# ESP_Circuit.net
KiCad netlist of a schematic drawn in Altium Designer
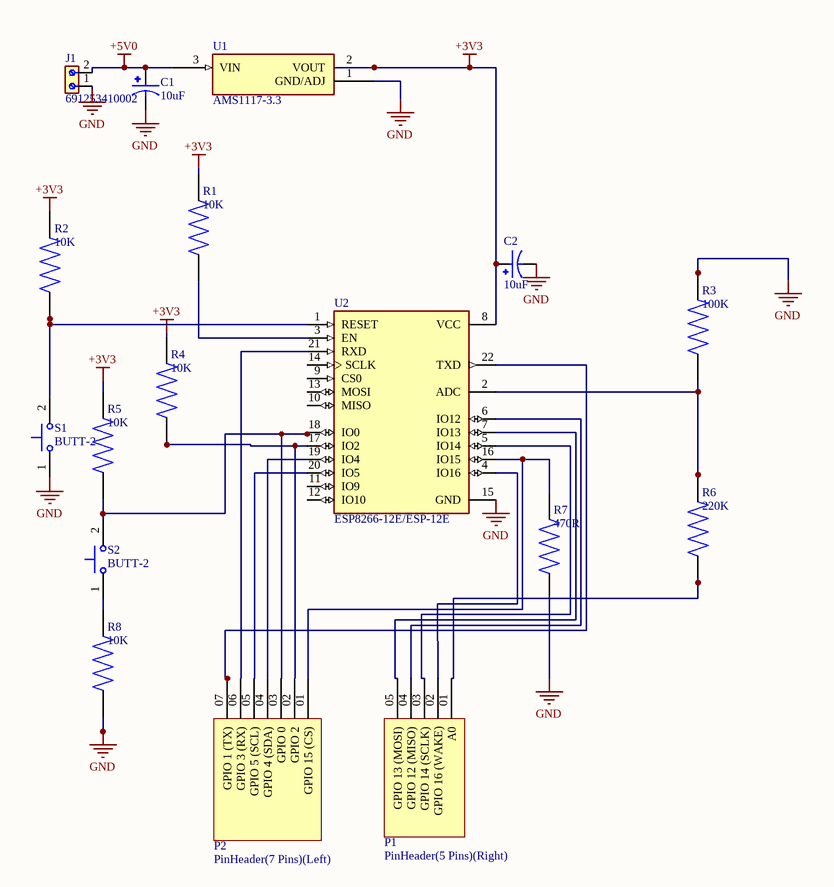
[diagram p0: ESP_Circuit.SchDoc]

(export (version "E")
  (design (tool "Eeschema 10.0.6"))
  (components
    (comp (ref "C1")
      (value "10uF")
      (footprint "CAPPRD500W60D1000H2000")
      (description "Aluminum Electrolytic Capacitors - Radial Leaded 10uF 350volts AEC-Q200")
      (fields (field (name "MF") "Panasonic") (field (name "MP") "EEU-EB2V100B"))
      (libsource (lib "MegaProject_Lib") (part "EEUEB2V100B"))
    )
    (comp (ref "C2")
      (value "10uF")
      (footprint "CAPPRD500W60D1000H2000")
      (description "Aluminum Electrolytic Capacitors - Radial Leaded 10uF 350volts AEC-Q200")
      (fields (field (name "MF") "Panasonic") (field (name "MP") "EEU-EB2V100B"))
      (libsource (lib "") (part "EEUEB2V100B_1"))
    )
    (comp (ref "J1")
      (value "691253410002")
      (footprint "691253410002")
      (description "7.62 MM TERMINAL BLOCK, HORIZONT")
      (fields (field (name "MF") "WÃ¼rth Elektronik"))
      (libsource (lib "MegaProject_Lib") (part "691253410002"))
    )
    (comp (ref "P1")
      (value "PinHeader(5 Pins)(Right)")
      (footprint "5 pins connector")
      (libsource (lib "MegaProject_Lib") (part "PinHeader(5 Pins)(Right)"))
    )
    (comp (ref "P2")
      (value "PinHeader(7 Pins)(Left)")
      (footprint "7 pins connector")
      (libsource (lib "MegaProject_Lib") (part "PinHeader(7 Pins)(Left)"))
    )
    (comp (ref "R1")
      (value "10K")
      (footprint "RESAD1100W55L680D260")
      (description "RES 280K OHM 1/4W 1% AXIAL")
      (fields (field (name "MP") "MFR-25FBF52-3K16"))
      (libsource (lib "MegaProject_Lib") (part "MFR-25FBF52-3K16"))
    )
    (comp (ref "R2")
      (value "10K")
      (footprint "RESAD1100W55L680D260")
      (description "RES 280K OHM 1/4W 1% AXIAL")
      (fields (field (name "MP") "MFR-25FBF52-3K16"))
      (libsource (lib "MegaProject_Lib") (part "MFR-25FBF52-3K16"))
    )
    (comp (ref "R3")
      (value "100K")
      (footprint "RESAD1100W55L680D260")
      (description "RES 280K OHM 1/4W 1% AXIAL")
      (fields (field (name "MP") "MFR-25FBF52-3K16"))
      (libsource (lib "MegaProject_Lib") (part "MFR-25FBF52-3K16"))
    )
    (comp (ref "R4")
      (value "10K")
      (footprint "RESAD1100W55L680D260")
      (description "RES 280K OHM 1/4W 1% AXIAL")
      (fields (field (name "MP") "MFR-25FBF52-3K16"))
      (libsource (lib "MegaProject_Lib") (part "MFR-25FBF52-3K16"))
    )
    (comp (ref "R5")
      (value "10K")
      (footprint "RESAD1100W55L680D260")
      (description "RES 280K OHM 1/4W 1% AXIAL")
      (fields (field (name "MP") "MFR-25FBF52-3K16"))
      (libsource (lib "MegaProject_Lib") (part "MFR-25FBF52-3K16"))
    )
    (comp (ref "R6")
      (value "220K")
      (footprint "RESAD1100W55L680D260")
      (description "RES 280K OHM 1/4W 1% AXIAL")
      (fields (field (name "MP") "MFR-25FBF52-3K16"))
      (libsource (lib "MegaProject_Lib") (part "MFR-25FBF52-3K16"))
    )
    (comp (ref "R7")
      (value "470R")
      (footprint "RESAD1100W55L680D260")
      (description "RES 280K OHM 1/4W 1% AXIAL")
      (fields (field (name "MP") "MFR-25FBF52-3K16"))
      (libsource (lib "MegaProject_Lib") (part "MFR-25FBF52-3K16"))
    )
    (comp (ref "R8")
      (value "10K")
      (footprint "RESAD1100W55L680D260")
      (description "RES 280K OHM 1/4W 1% AXIAL")
      (fields (field (name "MP") "MFR-25FBF52-3K16"))
      (libsource (lib "MegaProject_Lib") (part "MFR-25FBF52-3K16"))
    )
    (comp (ref "S1")
      (value "BUTT-2")
      (footprint "SW_BUTT-2")
      (description "Tactile Switches MINI PUSH BUTTON SWITCH 2-PIN QTY. 4")
      (fields (field (name "MF") "Gravitech"))
      (libsource (lib "MegaProject_Lib") (part "BUTT-2"))
    )
    (comp (ref "S2")
      (value "BUTT-2")
      (footprint "SW_BUTT-2")
      (description "Tactile Switches MINI PUSH BUTTON SWITCH 2-PIN QTY. 4")
      (fields (field (name "MF") "Gravitech"))
      (libsource (lib "MegaProject_Lib") (part "BUTT-2"))
    )
    (comp (ref "U1")
      (value "AMS1117-3.3")
      (footprint "SOT229P700X180-4N")
      (description "Sot223/Pkg 1-Amp 3.3-Volt Low Drop Out Voltage Regulatator")
      (fields (field (name "MF") "Advanced Monolithic Systems"))
      (libsource (lib "MegaProject_Lib") (part "AMS1117-3.3"))
    )
    (comp (ref "U2")
      (value "ESP8266-12E/ESP-12E")
      (footprint "XCVR_ESP8266-12E/ESP-12E")
      (fields (field (name "MF") "AI-Thinker"))
      (libsource (lib "MegaProject_Lib") (part "ESP8266-12E/ESP-12E"))
    )
  )
  (nets
    (net (code "1") (name "+3V3") (class "Default")
      (node (ref "C2") (pin "P") (pinfunction "P_P") (pintype "passive"))
      (node (ref "R1") (pin "2") (pinfunction "2_2") (pintype "passive"))
      (node (ref "R2") (pin "2") (pinfunction "2_2") (pintype "passive"))
      (node (ref "R4") (pin "2") (pinfunction "2_2") (pintype "passive"))
      (node (ref "R5") (pin "2") (pinfunction "2_2") (pintype "passive"))
      (node (ref "U1") (pin "2") (pinfunction "VOUT_2") (pintype "power_in"))
      (node (ref "U2") (pin "8") (pinfunction "VCC_8") (pintype "power_in"))
    )
    (net (code "2") (name "+5V0") (class "Default")
      (node (ref "C1") (pin "P") (pinfunction "P_P") (pintype "passive"))
      (node (ref "J1") (pin "2") (pinfunction "2_2") (pintype "passive"))
      (node (ref "U1") (pin "3") (pinfunction "VIN_3") (pintype "input"))
    )
    (net (code "3") (name "GND") (class "Default")
      (node (ref "C1") (pin "N") (pinfunction "N_N") (pintype "passive"))
      (node (ref "C2") (pin "N") (pinfunction "N_N") (pintype "passive"))
      (node (ref "J1") (pin "1") (pinfunction "1_1") (pintype "passive"))
      (node (ref "R3") (pin "2") (pinfunction "2_2") (pintype "passive"))
      (node (ref "R7") (pin "1") (pinfunction "1_1") (pintype "passive"))
      (node (ref "R8") (pin "1") (pinfunction "1_1") (pintype "passive"))
      (node (ref "S1") (pin "1") (pinfunction "1_1") (pintype "passive"))
      (node (ref "U1") (pin "1") (pinfunction "GND/ADJ_1") (pintype "power_in"))
      (node (ref "U2") (pin "15") (pinfunction "GND_15") (pintype "power_in"))
    )
    (net (code "4") (name "Net-(P1-A0)") (class "Default")
      (node (ref "P1") (pin "01") (pinfunction "A0_01") (pintype "passive"))
      (node (ref "R6") (pin "1") (pinfunction "1_1") (pintype "passive"))
    )
    (net (code "5") (name "Net-(P1-GPIO_12_(MISO))") (class "Default")
      (node (ref "P1") (pin "04") (pinfunction "GPIO_12_(MISO)_04") (pintype "passive"))
      (node (ref "U2") (pin "6") (pinfunction "IO12_6") (pintype "bidirectional"))
    )
    (net (code "6") (name "Net-(P1-GPIO_13_(MOSI))") (class "Default")
      (node (ref "P1") (pin "05") (pinfunction "GPIO_13_(MOSI)_05") (pintype "passive"))
      (node (ref "U2") (pin "7") (pinfunction "IO13_7") (pintype "bidirectional"))
    )
    (net (code "7") (name "Net-(P1-GPIO_14_(SCLK))") (class "Default")
      (node (ref "P1") (pin "03") (pinfunction "GPIO_14_(SCLK)_03") (pintype "passive"))
      (node (ref "U2") (pin "5") (pinfunction "IO14_5") (pintype "bidirectional"))
    )
    (net (code "8") (name "Net-(P1-GPIO_16_(WAKE))") (class "Default")
      (node (ref "P1") (pin "02") (pinfunction "GPIO_16_(WAKE)_02") (pintype "passive"))
      (node (ref "U2") (pin "4") (pinfunction "IO16_4") (pintype "bidirectional"))
    )
    (net (code "9") (name "Net-(P2-GPIO_0)") (class "Default")
      (node (ref "P2") (pin "03") (pinfunction "GPIO_0_03") (pintype "passive"))
      (node (ref "R5") (pin "1") (pinfunction "1_1") (pintype "passive"))
      (node (ref "S2") (pin "2") (pinfunction "2_2") (pintype "passive"))
      (node (ref "U2") (pin "18") (pinfunction "IO0_18") (pintype "bidirectional"))
    )
    (net (code "10") (name "Net-(P2-GPIO_1_(TX))") (class "Default")
      (node (ref "P2") (pin "07") (pinfunction "GPIO_1_(TX)_07") (pintype "passive"))
      (node (ref "U2") (pin "22") (pinfunction "TXD_22") (pintype "output"))
    )
    (net (code "11") (name "Net-(P2-GPIO_2)") (class "Default")
      (node (ref "P2") (pin "02") (pinfunction "GPIO_2_02") (pintype "passive"))
      (node (ref "R4") (pin "1") (pinfunction "1_1") (pintype "passive"))
      (node (ref "U2") (pin "17") (pinfunction "IO2_17") (pintype "bidirectional"))
    )
    (net (code "12") (name "Net-(P2-GPIO_3_(RX))") (class "Default")
      (node (ref "P2") (pin "06") (pinfunction "GPIO_3_(RX)_06") (pintype "passive"))
      (node (ref "U2") (pin "21") (pinfunction "RXD_21") (pintype "input"))
    )
    (net (code "13") (name "Net-(P2-GPIO_4_(SDA))") (class "Default")
      (node (ref "P2") (pin "04") (pinfunction "GPIO_4_(SDA)_04") (pintype "passive"))
      (node (ref "U2") (pin "19") (pinfunction "IO4_19") (pintype "bidirectional"))
    )
    (net (code "14") (name "Net-(P2-GPIO_5_(SCL))") (class "Default")
      (node (ref "P2") (pin "05") (pinfunction "GPIO_5_(SCL)_05") (pintype "passive"))
      (node (ref "U2") (pin "20") (pinfunction "IO5_20") (pintype "bidirectional"))
    )
    (net (code "15") (name "Net-(P2-GPIO_15_(CS))") (class "Default")
      (node (ref "P2") (pin "01") (pinfunction "GPIO_15_(CS)_01") (pintype "passive"))
      (node (ref "R7") (pin "2") (pinfunction "2_2") (pintype "passive"))
      (node (ref "U2") (pin "16") (pinfunction "IO15_16") (pintype "bidirectional"))
    )
    (net (code "16") (name "Net-(R8-Pad2)") (class "Default")
      (node (ref "R8") (pin "2") (pinfunction "2_2") (pintype "passive"))
      (node (ref "S2") (pin "1") (pinfunction "1_1") (pintype "passive"))
    )
    (net (code "17") (name "Net-(U2-ADC)") (class "Default")
      (node (ref "R3") (pin "1") (pinfunction "1_1") (pintype "passive"))
      (node (ref "R6") (pin "2") (pinfunction "2_2") (pintype "passive"))
      (node (ref "U2") (pin "2") (pinfunction "ADC_2") (pintype "passive"))
    )
    (net (code "18") (name "Net-(U2-EN)") (class "Default")
      (node (ref "R1") (pin "1") (pinfunction "1_1") (pintype "passive"))
      (node (ref "U2") (pin "3") (pinfunction "EN_3") (pintype "input"))
    )
    (net (code "19") (name "Net-(U2-RESET)") (class "Default")
      (node (ref "R2") (pin "1") (pinfunction "1_1") (pintype "passive"))
      (node (ref "S1") (pin "2") (pinfunction "2_2") (pintype "passive"))
      (node (ref "U2") (pin "1") (pinfunction "RESET_1") (pintype "input"))
    )
    (net (code "20") (name "unconnected-(U2-CS0-Pad9)") (class "Default")
      (node (ref "U2") (pin "9") (pinfunction "CS0_9") (pintype "input"))
    )
    (net (code "21") (name "unconnected-(U2-IO9-Pad11)") (class "Default")
      (node (ref "U2") (pin "11") (pinfunction "IO9_11") (pintype "bidirectional"))
    )
    (net (code "22") (name "unconnected-(U2-IO10-Pad12)") (class "Default")
      (node (ref "U2") (pin "12") (pinfunction "IO10_12") (pintype "bidirectional"))
    )
    (net (code "23") (name "unconnected-(U2-MISO-Pad10)") (class "Default")
      (node (ref "U2") (pin "10") (pinfunction "MISO_10") (pintype "bidirectional"))
    )
    (net (code "24") (name "unconnected-(U2-MOSI-Pad13)") (class "Default")
      (node (ref "U2") (pin "13") (pinfunction "MOSI_13") (pintype "bidirectional"))
    )
    (net (code "25") (name "unconnected-(U2-SCLK-Pad14)") (class "Default")
      (node (ref "U2") (pin "14") (pinfunction "SCLK_14") (pintype "input"))
    )
  )
)
